# DMX_Shield_3_universe.net
KiCad netlist of a schematic drawn in EasyEDA
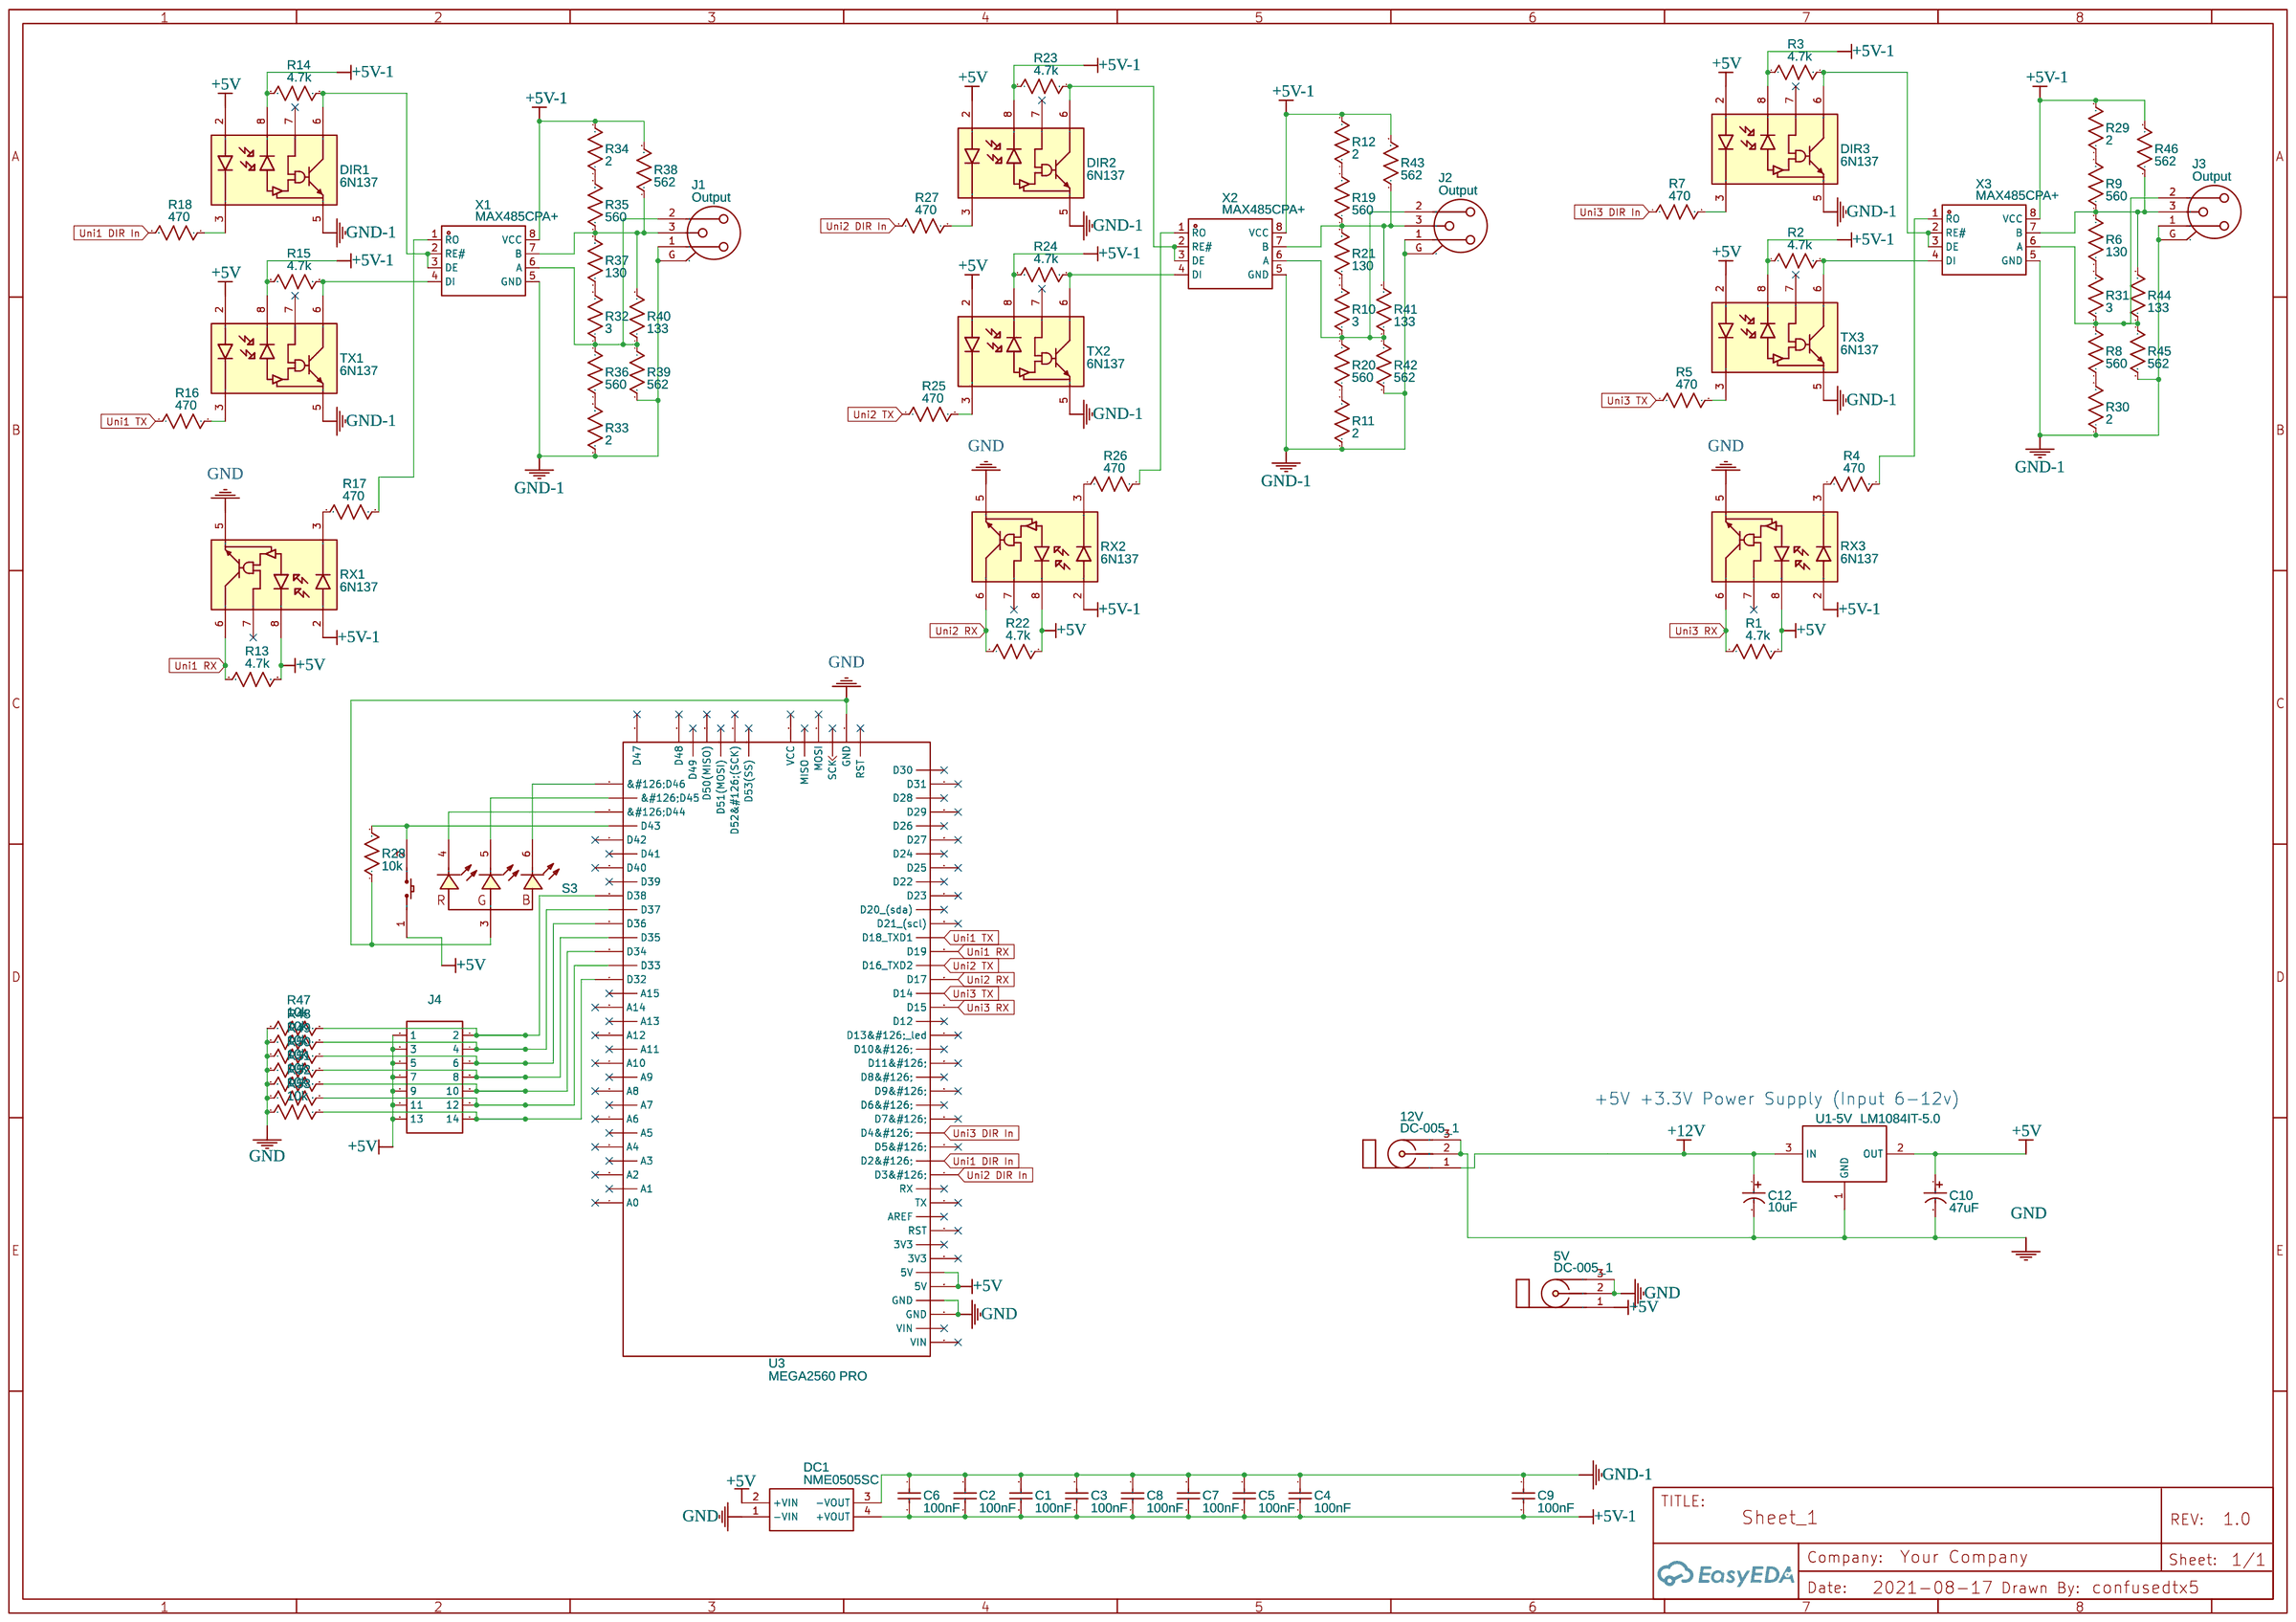
[diagram p0: schematic sheet]

(export (version "E")
  (design (tool "Eeschema 10.0.6"))
  (components
    (comp (ref "5V") (value "DC-005_1") (libsource (lib "") (part "Unknown_1125_-315")))
    (comp (ref "12V") (value "DC-005_1") (libsource (lib "") (part "Unknown_1015_-415")))
    (comp (ref "C1")
      (value "100nF")
      (fields
        (field (name "BOM_Manufacturer Part") "SR211C104KAR")
        (field (name "BOM_Supplier Part") "C444738")
      )
      (libsource (lib "") (part "SR211C104KAR"))
    )
    (comp (ref "C2")
      (value "100nF")
      (fields
        (field (name "BOM_Manufacturer Part") "SR211C104KAR")
        (field (name "BOM_Supplier Part") "C444738")
      )
      (libsource (lib "") (part "SR211C104KAR"))
    )
    (comp (ref "C3")
      (value "100nF")
      (fields
        (field (name "BOM_Manufacturer Part") "SR211C104KAR")
        (field (name "BOM_Supplier Part") "C444738")
      )
      (libsource (lib "") (part "SR211C104KAR"))
    )
    (comp (ref "C4")
      (value "100nF")
      (fields
        (field (name "BOM_Manufacturer Part") "SR211C104KAR")
        (field (name "BOM_Supplier Part") "C444738")
      )
      (libsource (lib "") (part "SR211C104KAR"))
    )
    (comp (ref "C5")
      (value "100nF")
      (fields
        (field (name "BOM_Manufacturer Part") "SR211C104KAR")
        (field (name "BOM_Supplier Part") "C444738")
      )
      (libsource (lib "") (part "SR211C104KAR"))
    )
    (comp (ref "C6")
      (value "100nF")
      (fields
        (field (name "BOM_Manufacturer Part") "SR211C104KAR")
        (field (name "BOM_Supplier Part") "C444738")
      )
      (libsource (lib "") (part "SR211C104KAR"))
    )
    (comp (ref "C7")
      (value "100nF")
      (fields
        (field (name "BOM_Manufacturer Part") "SR211C104KAR")
        (field (name "BOM_Supplier Part") "C444738")
      )
      (libsource (lib "") (part "SR211C104KAR"))
    )
    (comp (ref "C8")
      (value "100nF")
      (fields
        (field (name "BOM_Manufacturer Part") "SR211C104KAR")
        (field (name "BOM_Supplier Part") "C444738")
      )
      (libsource (lib "") (part "SR211C104KAR"))
    )
    (comp (ref "C9")
      (value "100nF")
      (fields
        (field (name "BOM_Manufacturer Part") "SR211C104KAR")
        (field (name "BOM_Supplier Part") "C444738")
      )
      (libsource (lib "") (part "SR211C104KAR"))
    )
    (comp (ref "C10")
      (value "47uF")
      (fields (field (name "BOM_Manufacturer Part") "47UF16V") (field (name "BOM_Supplier Part") "C30224"))
      (libsource (lib "") (part "47UF16V"))
    )
    (comp (ref "C12")
      (value "10uF")
      (fields
        (field (name "BOM_Manufacturer Part") "10uF 25V RHOS")
        (field (name "BOM_Supplier Part") "C19576")
      )
      (libsource (lib "") (part "Unknown_1235_-385"))
    )
    (comp (ref "DC1") (value "NME0505SC") (libsource (lib "") (part "NME0505SC")))
    (comp (ref "DIR1") (value "6N137") (libsource (lib "") (part "6N137")))
    (comp (ref "DIR2") (value "6N137") (libsource (lib "") (part "6N137")))
    (comp (ref "DIR3") (value "6N137") (libsource (lib "") (part "6N137")))
    (comp (ref "J1")
      (value "Output")
      (fields (field (name "BOM_Manufacturer Part") "XLR-328-2") (field (name "BOM_Supplier Part") "C309331"))
      (libsource (lib "") (part "XLR-328-2"))
    )
    (comp (ref "J2")
      (value "Output")
      (fields (field (name "BOM_Manufacturer Part") "XLR-328-2") (field (name "BOM_Supplier Part") "C309331"))
      (libsource (lib "") (part "XLR-328-2"))
    )
    (comp (ref "J3")
      (value "Output")
      (fields (field (name "BOM_Manufacturer Part") "XLR-328-2") (field (name "BOM_Supplier Part") "C309331"))
      (libsource (lib "") (part "XLR-328-2"))
    )
    (comp (ref "J4")
      (value "Header-Male-2.54_2x7")
      (fields
        (field (name "BOM_Manufacturer Part") "Double row of needle2X7P 2.54mm")
        (field (name "BOM_Supplier Part") "C71397")
      )
      (libsource (lib "") (part "Header-Male-2.54_2x7"))
    )
    (comp (ref "R1") (value "4.7k") (libsource (lib "") (part "R_0805_US_1")))
    (comp (ref "R2") (value "4.7k") (libsource (lib "") (part "R_0805_US_1")))
    (comp (ref "R3") (value "4.7k") (libsource (lib "") (part "R_0805_US_1")))
    (comp (ref "R4") (value "470") (libsource (lib "") (part "R_0805_US_1")))
    (comp (ref "R5") (value "470") (libsource (lib "") (part "R_0805_US_1")))
    (comp (ref "R6") (value "130") (libsource (lib "") (part "R_0805_US")))
    (comp (ref "R7") (value "470") (libsource (lib "") (part "R_0805_US_1")))
    (comp (ref "R8") (value "560") (libsource (lib "") (part "R_0805_US")))
    (comp (ref "R9") (value "560") (libsource (lib "") (part "R_0805_US")))
    (comp (ref "R10") (value "3") (libsource (lib "") (part "R_0805_US")))
    (comp (ref "R11") (value "2") (libsource (lib "") (part "R_0805_US")))
    (comp (ref "R12") (value "2") (libsource (lib "") (part "R_0805_US")))
    (comp (ref "R13") (value "4.7k") (libsource (lib "") (part "R_0805_US_1")))
    (comp (ref "R14") (value "4.7k") (libsource (lib "") (part "R_0805_US_1")))
    (comp (ref "R15") (value "4.7k") (libsource (lib "") (part "R_0805_US_1")))
    (comp (ref "R16") (value "470") (libsource (lib "") (part "R_0805_US_1")))
    (comp (ref "R17") (value "470") (libsource (lib "") (part "R_0805_US_1")))
    (comp (ref "R18") (value "470") (libsource (lib "") (part "R_0805_US_1")))
    (comp (ref "R19") (value "560") (libsource (lib "") (part "R_0805_US")))
    (comp (ref "R20") (value "560") (libsource (lib "") (part "R_0805_US")))
    (comp (ref "R21") (value "130") (libsource (lib "") (part "R_0805_US")))
    (comp (ref "R22") (value "4.7k") (libsource (lib "") (part "R_0805_US_1")))
    (comp (ref "R23") (value "4.7k") (libsource (lib "") (part "R_0805_US_1")))
    (comp (ref "R24") (value "4.7k") (libsource (lib "") (part "R_0805_US_1")))
    (comp (ref "R25") (value "470") (libsource (lib "") (part "R_0805_US_1")))
    (comp (ref "R26") (value "470") (libsource (lib "") (part "R_0805_US_1")))
    (comp (ref "R27") (value "470") (libsource (lib "") (part "R_0805_US_1")))
    (comp (ref "R28") (value "10k") (libsource (lib "") (part "R_0805_US")))
    (comp (ref "R29") (value "2") (libsource (lib "") (part "R_0805_US")))
    (comp (ref "R30") (value "2") (libsource (lib "") (part "R_0805_US")))
    (comp (ref "R31") (value "3") (libsource (lib "") (part "R_0805_US")))
    (comp (ref "R32") (value "3") (libsource (lib "") (part "R_0805_US")))
    (comp (ref "R33") (value "2") (libsource (lib "") (part "R_0805_US")))
    (comp (ref "R34") (value "2") (libsource (lib "") (part "R_0805_US")))
    (comp (ref "R35") (value "560") (libsource (lib "") (part "R_0805_US")))
    (comp (ref "R36") (value "560") (libsource (lib "") (part "R_0805_US")))
    (comp (ref "R37") (value "130") (libsource (lib "") (part "R_0805_US")))
    (comp (ref "R38") (value "562") (libsource (lib "") (part "R_0805_US")))
    (comp (ref "R39") (value "562") (libsource (lib "") (part "R_0805_US_2")))
    (comp (ref "R40") (value "133") (libsource (lib "") (part "R_0805_US")))
    (comp (ref "R41") (value "133") (libsource (lib "") (part "R_0805_US")))
    (comp (ref "R42") (value "562") (libsource (lib "") (part "R_0805_US_2")))
    (comp (ref "R43") (value "562") (libsource (lib "") (part "R_0805_US")))
    (comp (ref "R44") (value "133") (libsource (lib "") (part "R_0805_US")))
    (comp (ref "R45") (value "562") (libsource (lib "") (part "R_0805_US_2")))
    (comp (ref "R46") (value "562") (libsource (lib "") (part "R_0805_US")))
    (comp (ref "R47") (value "10k") (libsource (lib "") (part "R_0805_US_1")))
    (comp (ref "R48") (value "10k") (libsource (lib "") (part "R_0805_US_1")))
    (comp (ref "R49") (value "10k") (libsource (lib "") (part "R_0805_US_1")))
    (comp (ref "R50") (value "10k") (libsource (lib "") (part "R_0805_US_1")))
    (comp (ref "R51") (value "10k") (libsource (lib "") (part "R_0805_US_1")))
    (comp (ref "R52") (value "10k") (libsource (lib "") (part "R_0805_US_1")))
    (comp (ref "R53") (value "10k") (libsource (lib "") (part "R_0805_US_1")))
    (comp (ref "RX1") (value "6N137") (libsource (lib "") (part "6N137_1")))
    (comp (ref "RX2") (value "6N137") (libsource (lib "") (part "6N137_1")))
    (comp (ref "RX3") (value "6N137") (libsource (lib "") (part "6N137_1")))
    (comp (ref "S3") (value "RGB CA MOMENTARY BUTTON") (libsource (lib "") (part "RGB CA MOMENTARY BUTTON")))
    (comp (ref "TX1") (value "6N137") (libsource (lib "") (part "6N137_2")))
    (comp (ref "TX2") (value "6N137") (libsource (lib "") (part "6N137_2")))
    (comp (ref "TX3") (value "6N137") (libsource (lib "") (part "6N137_2")))
    (comp (ref "U1-5V")
      (value "LM1084IT-5.0")
      (fields (field (name "BOM_Supplier Part") "C9719"))
      (libsource (lib "") (part "LM1084IT-5.0"))
    )
    (comp (ref "U3")
      (value "MEGA2560 PRO")
      (fields (field (name "BOM_Manufacturer Part") "MEGA2560 PRO-ch340G"))
      (libsource (lib "") (part "MEGA2560 PRO"))
    )
    (comp (ref "X1")
      (value "MAX485CPA+")
      (fields (field (name "BOM_Supplier Part") "C77792"))
      (libsource (lib "") (part "MAX485CPA+"))
    )
    (comp (ref "X2")
      (value "MAX485CPA+")
      (fields (field (name "BOM_Supplier Part") "C77792"))
      (libsource (lib "") (part "MAX485CPA+"))
    )
    (comp (ref "X3")
      (value "MAX485CPA+")
      (fields (field (name "BOM_Supplier Part") "C77792"))
      (libsource (lib "") (part "MAX485CPA+"))
    )
  )
  (nets
    (net (code "1") (name "+5V") (class "Default")
      (node (ref "5V") (pin "1") (pinfunction "1_1") (pintype "input"))
      (node (ref "C10") (pin "1") (pinfunction "1_1") (pintype "input"))
      (node (ref "DC1") (pin "2") (pinfunction "+VIN_2") (pintype "unspecified"))
      (node (ref "DIR1") (pin "2") (pinfunction "2_2") (pintype "unspecified"))
      (node (ref "DIR2") (pin "2") (pinfunction "2_2") (pintype "unspecified"))
      (node (ref "DIR3") (pin "2") (pinfunction "2_2") (pintype "unspecified"))
      (node (ref "J4") (pin "1") (pinfunction "1_1") (pintype "input"))
      (node (ref "J4") (pin "11") (pinfunction "11_11") (pintype "input"))
      (node (ref "J4") (pin "13") (pinfunction "13_13") (pintype "input"))
      (node (ref "J4") (pin "3") (pinfunction "3_3") (pintype "input"))
      (node (ref "J4") (pin "5") (pinfunction "5_5") (pintype "input"))
      (node (ref "J4") (pin "7") (pinfunction "7_7") (pintype "input"))
      (node (ref "J4") (pin "9") (pinfunction "9_9") (pintype "input"))
      (node (ref "R1") (pin "2") (pinfunction "2_2") (pintype "unspecified"))
      (node (ref "R13") (pin "2") (pinfunction "2_2") (pintype "unspecified"))
      (node (ref "R22") (pin "2") (pinfunction "2_2") (pintype "unspecified"))
      (node (ref "RX1") (pin "8") (pinfunction "8_8") (pintype "unspecified"))
      (node (ref "RX2") (pin "8") (pinfunction "8_8") (pintype "unspecified"))
      (node (ref "RX3") (pin "8") (pinfunction "8_8") (pintype "unspecified"))
      (node (ref "S3") (pin "1") (pinfunction "NO1_1") (pintype "unspecified"))
      (node (ref "TX1") (pin "2") (pinfunction "2_2") (pintype "unspecified"))
      (node (ref "TX2") (pin "2") (pinfunction "2_2") (pintype "unspecified"))
      (node (ref "TX3") (pin "2") (pinfunction "2_2") (pintype "unspecified"))
      (node (ref "U1-5V") (pin "2") (pinfunction "OUT_2") (pintype "passive"))
      (node (ref "U3") (pin "81") (pinfunction "5V_81") (pintype "unspecified"))
      (node (ref "U3") (pin "82") (pinfunction "5V_82") (pintype "unspecified"))
    )
    (net (code "2") (name "+5V-1") (class "Default")
      (node (ref "C1") (pin "2") (pinfunction "2_2") (pintype "input"))
      (node (ref "C2") (pin "2") (pinfunction "2_2") (pintype "input"))
      (node (ref "C3") (pin "2") (pinfunction "2_2") (pintype "input"))
      (node (ref "C4") (pin "2") (pinfunction "2_2") (pintype "input"))
      (node (ref "C5") (pin "2") (pinfunction "2_2") (pintype "input"))
      (node (ref "C6") (pin "2") (pinfunction "2_2") (pintype "input"))
      (node (ref "C7") (pin "2") (pinfunction "2_2") (pintype "input"))
      (node (ref "C8") (pin "2") (pinfunction "2_2") (pintype "input"))
      (node (ref "C9") (pin "2") (pinfunction "2_2") (pintype "input"))
      (node (ref "DC1") (pin "4") (pinfunction "+VOUT_4") (pintype "unspecified"))
      (node (ref "DIR1") (pin "8") (pinfunction "8_8") (pintype "unspecified"))
      (node (ref "DIR2") (pin "8") (pinfunction "8_8") (pintype "unspecified"))
      (node (ref "DIR3") (pin "8") (pinfunction "8_8") (pintype "unspecified"))
      (node (ref "R12") (pin "2") (pinfunction "2_2") (pintype "unspecified"))
      (node (ref "R14") (pin "1") (pinfunction "1_1") (pintype "unspecified"))
      (node (ref "R15") (pin "1") (pinfunction "1_1") (pintype "unspecified"))
      (node (ref "R2") (pin "1") (pinfunction "1_1") (pintype "unspecified"))
      (node (ref "R23") (pin "1") (pinfunction "1_1") (pintype "unspecified"))
      (node (ref "R24") (pin "1") (pinfunction "1_1") (pintype "unspecified"))
      (node (ref "R29") (pin "2") (pinfunction "2_2") (pintype "unspecified"))
      (node (ref "R3") (pin "1") (pinfunction "1_1") (pintype "unspecified"))
      (node (ref "R34") (pin "2") (pinfunction "2_2") (pintype "unspecified"))
      (node (ref "R38") (pin "2") (pinfunction "2_2") (pintype "unspecified"))
      (node (ref "R43") (pin "2") (pinfunction "2_2") (pintype "unspecified"))
      (node (ref "R46") (pin "2") (pinfunction "2_2") (pintype "unspecified"))
      (node (ref "RX1") (pin "2") (pinfunction "2_2") (pintype "unspecified"))
      (node (ref "RX2") (pin "2") (pinfunction "2_2") (pintype "unspecified"))
      (node (ref "RX3") (pin "2") (pinfunction "2_2") (pintype "unspecified"))
      (node (ref "TX1") (pin "8") (pinfunction "8_8") (pintype "unspecified"))
      (node (ref "TX2") (pin "8") (pinfunction "8_8") (pintype "unspecified"))
      (node (ref "TX3") (pin "8") (pinfunction "8_8") (pintype "unspecified"))
      (node (ref "X1") (pin "8") (pinfunction "VCC_8") (pintype "unspecified"))
      (node (ref "X2") (pin "8") (pinfunction "VCC_8") (pintype "unspecified"))
      (node (ref "X3") (pin "8") (pinfunction "VCC_8") (pintype "unspecified"))
    )
    (net (code "3") (name "+12V") (class "Default")
      (node (ref "12V") (pin "1") (pinfunction "1_1") (pintype "input"))
      (node (ref "C12") (pin "1") (pinfunction "1_1") (pintype "input"))
      (node (ref "U1-5V") (pin "3") (pinfunction "IN_3") (pintype "passive"))
    )
    (net (code "4") (name "GND") (class "Default")
      (node (ref "12V") (pin "2") (pinfunction "VCC_2") (pintype "input"))
      (node (ref "12V") (pin "3") (pinfunction "3_3") (pintype "input"))
      (node (ref "5V") (pin "2") (pinfunction "VCC_2") (pintype "input"))
      (node (ref "5V") (pin "3") (pinfunction "3_3") (pintype "input"))
      (node (ref "C10") (pin "2") (pinfunction "2_2") (pintype "input"))
      (node (ref "C12") (pin "2") (pinfunction "2_2") (pintype "input"))
      (node (ref "DC1") (pin "1") (pinfunction "-VIN_1") (pintype "unspecified"))
      (node (ref "R28") (pin "1") (pinfunction "1_1") (pintype "unspecified"))
      (node (ref "R47") (pin "1") (pinfunction "1_1") (pintype "unspecified"))
      (node (ref "R48") (pin "1") (pinfunction "1_1") (pintype "unspecified"))
      (node (ref "R49") (pin "1") (pinfunction "1_1") (pintype "unspecified"))
      (node (ref "R50") (pin "1") (pinfunction "1_1") (pintype "unspecified"))
      (node (ref "R51") (pin "1") (pinfunction "1_1") (pintype "unspecified"))
      (node (ref "R52") (pin "1") (pinfunction "1_1") (pintype "unspecified"))
      (node (ref "R53") (pin "1") (pinfunction "1_1") (pintype "unspecified"))
      (node (ref "RX1") (pin "5") (pinfunction "5_5") (pintype "unspecified"))
      (node (ref "RX2") (pin "5") (pinfunction "5_5") (pintype "unspecified"))
      (node (ref "RX3") (pin "5") (pinfunction "5_5") (pintype "unspecified"))
      (node (ref "S3") (pin "3") (pinfunction "CA_3") (pintype "unspecified"))
      (node (ref "U1-5V") (pin "1") (pinfunction "GND_1") (pintype "passive"))
      (node (ref "U3") (pin "43") (pinfunction "GND_43") (pintype "unspecified"))
      (node (ref "U3") (pin "83") (pinfunction "GND_83") (pintype "unspecified"))
      (node (ref "U3") (pin "84") (pinfunction "GND_84") (pintype "unspecified"))
    )
    (net (code "5") (name "GND-1") (class "Default")
      (node (ref "C1") (pin "1") (pinfunction "1_1") (pintype "input"))
      (node (ref "C2") (pin "1") (pinfunction "1_1") (pintype "input"))
      (node (ref "C3") (pin "1") (pinfunction "1_1") (pintype "input"))
      (node (ref "C4") (pin "1") (pinfunction "1_1") (pintype "input"))
      (node (ref "C5") (pin "1") (pinfunction "1_1") (pintype "input"))
      (node (ref "C6") (pin "1") (pinfunction "1_1") (pintype "input"))
      (node (ref "C7") (pin "1") (pinfunction "1_1") (pintype "input"))
      (node (ref "C8") (pin "1") (pinfunction "1_1") (pintype "input"))
      (node (ref "C9") (pin "1") (pinfunction "1_1") (pintype "input"))
      (node (ref "DC1") (pin "3") (pinfunction "-VOUT_3") (pintype "unspecified"))
      (node (ref "DIR1") (pin "5") (pinfunction "5_5") (pintype "unspecified"))
      (node (ref "DIR2") (pin "5") (pinfunction "5_5") (pintype "unspecified"))
      (node (ref "DIR3") (pin "5") (pinfunction "5_5") (pintype "unspecified"))
      (node (ref "J1") (pin "1") (pinfunction "1_1") (pintype "unspecified"))
      (node (ref "J1") (pin "G") (pinfunction "G_G") (pintype "unspecified"))
      (node (ref "J2") (pin "1") (pinfunction "1_1") (pintype "unspecified"))
      (node (ref "J2") (pin "G") (pinfunction "G_G") (pintype "unspecified"))
      (node (ref "J3") (pin "1") (pinfunction "1_1") (pintype "unspecified"))
      (node (ref "J3") (pin "G") (pinfunction "G_G") (pintype "unspecified"))
      (node (ref "R11") (pin "1") (pinfunction "1_1") (pintype "unspecified"))
      (node (ref "R30") (pin "1") (pinfunction "1_1") (pintype "unspecified"))
      (node (ref "R33") (pin "1") (pinfunction "1_1") (pintype "unspecified"))
      (node (ref "R39") (pin "2") (pinfunction "2_2") (pintype "unspecified"))
      (node (ref "R42") (pin "2") (pinfunction "2_2") (pintype "unspecified"))
      (node (ref "R45") (pin "2") (pinfunction "2_2") (pintype "unspecified"))
      (node (ref "TX1") (pin "5") (pinfunction "5_5") (pintype "unspecified"))
      (node (ref "TX2") (pin "5") (pinfunction "5_5") (pintype "unspecified"))
      (node (ref "TX3") (pin "5") (pinfunction "5_5") (pintype "unspecified"))
      (node (ref "X1") (pin "5") (pinfunction "GND_5") (pintype "unspecified"))
      (node (ref "X2") (pin "5") (pinfunction "GND_5") (pintype "unspecified"))
      (node (ref "X3") (pin "5") (pinfunction "GND_5") (pintype "unspecified"))
    )
    (net (code "6") (name "Net-(DIR1-Pad3)") (class "Default")
      (node (ref "DIR1") (pin "3") (pinfunction "3_3") (pintype "unspecified"))
      (node (ref "R18") (pin "2") (pinfunction "2_2") (pintype "unspecified"))
    )
    (net (code "7") (name "Net-(DIR2-Pad3)") (class "Default")
      (node (ref "DIR2") (pin "3") (pinfunction "3_3") (pintype "unspecified"))
      (node (ref "R27") (pin "2") (pinfunction "2_2") (pintype "unspecified"))
    )
    (net (code "8") (name "Net-(DIR3-Pad3)") (class "Default")
      (node (ref "DIR3") (pin "3") (pinfunction "3_3") (pintype "unspecified"))
      (node (ref "R7") (pin "2") (pinfunction "2_2") (pintype "unspecified"))
    )
    (net (code "9") (name "Net-(R4-Pad1)") (class "Default")
      (node (ref "R4") (pin "1") (pinfunction "1_1") (pintype "unspecified"))
      (node (ref "RX3") (pin "3") (pinfunction "3_3") (pintype "unspecified"))
    )
    (net (code "10") (name "Net-(R5-Pad2)") (class "Default")
      (node (ref "R5") (pin "2") (pinfunction "2_2") (pintype "unspecified"))
      (node (ref "TX3") (pin "3") (pinfunction "3_3") (pintype "unspecified"))
    )
    (net (code "11") (name "Net-(R10-Pad2)") (class "Default")
      (node (ref "R10") (pin "2") (pinfunction "2_2") (pintype "unspecified"))
      (node (ref "R21") (pin "1") (pinfunction "1_1") (pintype "unspecified"))
    )
    (net (code "12") (name "Net-(R11-Pad2)") (class "Default")
      (node (ref "R11") (pin "2") (pinfunction "2_2") (pintype "unspecified"))
      (node (ref "R20") (pin "1") (pinfunction "1_1") (pintype "unspecified"))
    )
    (net (code "13") (name "Net-(R12-Pad1)") (class "Default")
      (node (ref "R12") (pin "1") (pinfunction "1_1") (pintype "unspecified"))
      (node (ref "R19") (pin "2") (pinfunction "2_2") (pintype "unspecified"))
    )
    (net (code "14") (name "Net-(R16-Pad2)") (class "Default")
      (node (ref "R16") (pin "2") (pinfunction "2_2") (pintype "unspecified"))
      (node (ref "TX1") (pin "3") (pinfunction "3_3") (pintype "unspecified"))
    )
    (net (code "15") (name "Net-(R17-Pad1)") (class "Default")
      (node (ref "R17") (pin "1") (pinfunction "1_1") (pintype "unspecified"))
      (node (ref "RX1") (pin "3") (pinfunction "3_3") (pintype "unspecified"))
    )
    (net (code "16") (name "Net-(R25-Pad2)") (class "Default")
      (node (ref "R25") (pin "2") (pinfunction "2_2") (pintype "unspecified"))
      (node (ref "TX2") (pin "3") (pinfunction "3_3") (pintype "unspecified"))
    )
    (net (code "17") (name "Net-(R26-Pad1)") (class "Default")
      (node (ref "R26") (pin "1") (pinfunction "1_1") (pintype "unspecified"))
      (node (ref "RX2") (pin "3") (pinfunction "3_3") (pintype "unspecified"))
    )
    (net (code "18") (name "Net-(R29-Pad1)") (class "Default")
      (node (ref "R29") (pin "1") (pinfunction "1_1") (pintype "unspecified"))
      (node (ref "R9") (pin "2") (pinfunction "2_2") (pintype "unspecified"))
    )
    (net (code "19") (name "Net-(R30-Pad2)") (class "Default")
      (node (ref "R30") (pin "2") (pinfunction "2_2") (pintype "unspecified"))
      (node (ref "R8") (pin "1") (pinfunction "1_1") (pintype "unspecified"))
    )
    (net (code "20") (name "Net-(R31-Pad2)") (class "Default")
      (node (ref "R31") (pin "2") (pinfunction "2_2") (pintype "unspecified"))
      (node (ref "R6") (pin "1") (pinfunction "1_1") (pintype "unspecified"))
    )
    (net (code "21") (name "Net-(R32-Pad2)") (class "Default")
      (node (ref "R32") (pin "2") (pinfunction "2_2") (pintype "unspecified"))
      (node (ref "R37") (pin "1") (pinfunction "1_1") (pintype "unspecified"))
    )
    (net (code "22") (name "Net-(R33-Pad2)") (class "Default")
      (node (ref "R33") (pin "2") (pinfunction "2_2") (pintype "unspecified"))
      (node (ref "R36") (pin "1") (pinfunction "1_1") (pintype "unspecified"))
    )
    (net (code "23") (name "Net-(R34-Pad1)") (class "Default")
      (node (ref "R34") (pin "1") (pinfunction "1_1") (pintype "unspecified"))
      (node (ref "R35") (pin "2") (pinfunction "2_2") (pintype "unspecified"))
    )
    (net (code "24") (name "Net-(S3-KB)") (class "Default")
      (node (ref "S3") (pin "6") (pinfunction "KB_6") (pintype "unspecified"))
      (node (ref "U3") (pin "31") (pinfunction "&#126;D46_31") (pintype "unspecified"))
    )
    (net (code "25") (name "Net-(S3-KG)") (class "Default")
      (node (ref "S3") (pin "5") (pinfunction "KG_5") (pintype "unspecified"))
      (node (ref "U3") (pin "30") (pinfunction "&#126;D45_30") (pintype "unspecified"))
    )
    (net (code "26") (name "Net-(S3-KR)") (class "Default")
      (node (ref "S3") (pin "4") (pinfunction "KR_4") (pintype "unspecified"))
      (node (ref "U3") (pin "29") (pinfunction "&#126;D44_29") (pintype "unspecified"))
    )
    (net (code "27") (name "Net-(S3-NO2)") (class "Default")
      (node (ref "R28") (pin "2") (pinfunction "2_2") (pintype "unspecified"))
      (node (ref "S3") (pin "2") (pinfunction "NO2_2") (pintype "unspecified"))
      (node (ref "U3") (pin "28") (pinfunction "D43_28") (pintype "unspecified"))
    )
    (net (code "28") (name "Net-(U3-D32)") (class "Default")
      (node (ref "J4") (pin "14") (pinfunction "14_14") (pintype "input"))
      (node (ref "R53") (pin "2") (pinfunction "2_2") (pintype "unspecified"))
      (node (ref "U3") (pin "17") (pinfunction "D32_17") (pintype "unspecified"))
    )
    (net (code "29") (name "Net-(U3-D33)") (class "Default")
      (node (ref "J4") (pin "12") (pinfunction "12_12") (pintype "input"))
      (node (ref "R52") (pin "2") (pinfunction "2_2") (pintype "unspecified"))
      (node (ref "U3") (pin "18") (pinfunction "D33_18") (pintype "unspecified"))
    )
    (net (code "30") (name "Net-(U3-D34)") (class "Default")
      (node (ref "J4") (pin "10") (pinfunction "10_10") (pintype "input"))
      (node (ref "R51") (pin "2") (pinfunction "2_2") (pintype "unspecified"))
      (node (ref "U3") (pin "19") (pinfunction "D34_19") (pintype "unspecified"))
    )
    (net (code "31") (name "Net-(U3-D35)") (class "Default")
      (node (ref "J4") (pin "8") (pinfunction "8_8") (pintype "input"))
      (node (ref "R50") (pin "2") (pinfunction "2_2") (pintype "unspecified"))
      (node (ref "U3") (pin "20") (pinfunction "D35_20") (pintype "unspecified"))
    )
    (net (code "32") (name "Net-(U3-D36)") (class "Default")
      (node (ref "J4") (pin "6") (pinfunction "6_6") (pintype "input"))
      (node (ref "R49") (pin "2") (pinfunction "2_2") (pintype "unspecified"))
      (node (ref "U3") (pin "21") (pinfunction "D36_21") (pintype "unspecified"))
    )
    (net (code "33") (name "Net-(U3-D37)") (class "Default")
      (node (ref "J4") (pin "4") (pinfunction "4_4") (pintype "input"))
      (node (ref "R48") (pin "2") (pinfunction "2_2") (pintype "unspecified"))
      (node (ref "U3") (pin "22") (pinfunction "D37_22") (pintype "unspecified"))
    )
    (net (code "34") (name "Net-(U3-D38)") (class "Default")
      (node (ref "J4") (pin "2") (pinfunction "2_2") (pintype "input"))
      (node (ref "R47") (pin "2") (pinfunction "2_2") (pintype "unspecified"))
      (node (ref "U3") (pin "23") (pinfunction "D38_23") (pintype "unspecified"))
    )
    (net (code "35") (name "Net-(X1-A)") (class "Default")
      (node (ref "J1") (pin "2") (pinfunction "2_2") (pintype "unspecified"))
      (node (ref "R32") (pin "1") (pinfunction "1_1") (pintype "unspecified"))
      (node (ref "R36") (pin "2") (pinfunction "2_2") (pintype "unspecified"))
      (node (ref "R39") (pin "1") (pinfunction "1_1") (pintype "unspecified"))
      (node (ref "R40") (pin "1") (pinfunction "1_1") (pintype "unspecified"))
      (node (ref "X1") (pin "6") (pinfunction "A_6") (pintype "unspecified"))
    )
    (net (code "36") (name "Net-(X1-B)") (class "Default")
      (node (ref "J1") (pin "3") (pinfunction "3_3") (pintype "unspecified"))
      (node (ref "R35") (pin "1") (pinfunction "1_1") (pintype "unspecified"))
      (node (ref "R37") (pin "2") (pinfunction "2_2") (pintype "unspecified"))
      (node (ref "R38") (pin "1") (pinfunction "1_1") (pintype "unspecified"))
      (node (ref "R40") (pin "2") (pinfunction "2_2") (pintype "unspecified"))
      (node (ref "X1") (pin "7") (pinfunction "B_7") (pintype "unspecified"))
    )
    (net (code "37") (name "Net-(X1-DE)") (class "Default")
      (node (ref "DIR1") (pin "6") (pinfunction "6_6") (pintype "output"))
      (node (ref "R14") (pin "2") (pinfunction "2_2") (pintype "unspecified"))
      (node (ref "X1") (pin "2") (pinfunction "RE#_2") (pintype "unspecified"))
      (node (ref "X1") (pin "3") (pinfunction "DE_3") (pintype "unspecified"))
    )
    (net (code "38") (name "Net-(X1-DI)") (class "Default")
      (node (ref "R15") (pin "2") (pinfunction "2_2") (pintype "unspecified"))
      (node (ref "TX1") (pin "6") (pinfunction "6_6") (pintype "output"))
      (node (ref "X1") (pin "4") (pinfunction "DI_4") (pintype "unspecified"))
    )
    (net (code "39") (name "Net-(X1-RO)") (class "Default")
      (node (ref "R17") (pin "2") (pinfunction "2_2") (pintype "unspecified"))
      (node (ref "X1") (pin "1") (pinfunction "RO_1") (pintype "unspecified"))
    )
    (net (code "40") (name "Net-(X2-A)") (class "Default")
      (node (ref "J2") (pin "2") (pinfunction "2_2") (pintype "unspecified"))
      (node (ref "R10") (pin "1") (pinfunction "1_1") (pintype "unspecified"))
      (node (ref "R20") (pin "2") (pinfunction "2_2") (pintype "unspecified"))
      (node (ref "R41") (pin "1") (pinfunction "1_1") (pintype "unspecified"))
      (node (ref "R42") (pin "1") (pinfunction "1_1") (pintype "unspecified"))
      (node (ref "X2") (pin "6") (pinfunction "A_6") (pintype "unspecified"))
    )
    (net (code "41") (name "Net-(X2-B)") (class "Default")
      (node (ref "J2") (pin "3") (pinfunction "3_3") (pintype "unspecified"))
      (node (ref "R19") (pin "1") (pinfunction "1_1") (pintype "unspecified"))
      (node (ref "R21") (pin "2") (pinfunction "2_2") (pintype "unspecified"))
      (node (ref "R41") (pin "2") (pinfunction "2_2") (pintype "unspecified"))
      (node (ref "R43") (pin "1") (pinfunction "1_1") (pintype "unspecified"))
      (node (ref "X2") (pin "7") (pinfunction "B_7") (pintype "unspecified"))
    )
    (net (code "42") (name "Net-(X2-DE)") (class "Default")
      (node (ref "DIR2") (pin "6") (pinfunction "6_6") (pintype "output"))
      (node (ref "R23") (pin "2") (pinfunction "2_2") (pintype "unspecified"))
      (node (ref "X2") (pin "2") (pinfunction "RE#_2") (pintype "unspecified"))
      (node (ref "X2") (pin "3") (pinfunction "DE_3") (pintype "unspecified"))
    )
    (net (code "43") (name "Net-(X2-DI)") (class "Default")
      (node (ref "R24") (pin "2") (pinfunction "2_2") (pintype "unspecified"))
      (node (ref "TX2") (pin "6") (pinfunction "6_6") (pintype "output"))
      (node (ref "X2") (pin "4") (pinfunction "DI_4") (pintype "unspecified"))
    )
    (net (code "44") (name "Net-(X2-RO)") (class "Default")
      (node (ref "R26") (pin "2") (pinfunction "2_2") (pintype "unspecified"))
      (node (ref "X2") (pin "1") (pinfunction "RO_1") (pintype "unspecified"))
    )
    (net (code "45") (name "Net-(X3-A)") (class "Default")
      (node (ref "J3") (pin "2") (pinfunction "2_2") (pintype "unspecified"))
      (node (ref "R31") (pin "1") (pinfunction "1_1") (pintype "unspecified"))
      (node (ref "R44") (pin "1") (pinfunction "1_1") (pintype "unspecified"))
      (node (ref "R45") (pin "1") (pinfunction "1_1") (pintype "unspecified"))
      (node (ref "R8") (pin "2") (pinfunction "2_2") (pintype "unspecified"))
      (node (ref "X3") (pin "6") (pinfunction "A_6") (pintype "unspecified"))
    )
    (net (code "46") (name "Net-(X3-B)") (class "Default")
      (node (ref "J3") (pin "3") (pinfunction "3_3") (pintype "unspecified"))
      (node (ref "R44") (pin "2") (pinfunction "2_2") (pintype "unspecified"))
      (node (ref "R46") (pin "1") (pinfunction "1_1") (pintype "unspecified"))
      (node (ref "R6") (pin "2") (pinfunction "2_2") (pintype "unspecified"))
      (node (ref "R9") (pin "1") (pinfunction "1_1") (pintype "unspecified"))
      (node (ref "X3") (pin "7") (pinfunction "B_7") (pintype "unspecified"))
    )
    (net (code "47") (name "Net-(X3-DE)") (class "Default")
      (node (ref "DIR3") (pin "6") (pinfunction "6_6") (pintype "output"))
      (node (ref "R3") (pin "2") (pinfunction "2_2") (pintype "unspecified"))
      (node (ref "X3") (pin "2") (pinfunction "RE#_2") (pintype "unspecified"))
      (node (ref "X3") (pin "3") (pinfunction "DE_3") (pintype "unspecified"))
    )
    (net (code "48") (name "Net-(X3-DI)") (class "Default")
      (node (ref "R2") (pin "2") (pinfunction "2_2") (pintype "unspecified"))
      (node (ref "TX3") (pin "6") (pinfunction "6_6") (pintype "output"))
      (node (ref "X3") (pin "4") (pinfunction "DI_4") (pintype "unspecified"))
    )
    (net (code "49") (name "Net-(X3-RO)") (class "Default")
      (node (ref "R4") (pin "2") (pinfunction "2_2") (pintype "unspecified"))
      (node (ref "X3") (pin "1") (pinfunction "RO_1") (pintype "unspecified"))
    )
    (net (code "50") (name "Uni1 DIR In") (class "Default")
      (node (ref "R18") (pin "1") (pinfunction "1_1") (pintype "unspecified"))
      (node (ref "U3") (pin "73") (pinfunction "D2&#126;_73") (pintype "unspecified"))
    )
    (net (code "51") (name "Uni1 RX") (class "Default")
      (node (ref "R13") (pin "1") (pinfunction "1_1") (pintype "unspecified"))
      (node (ref "RX1") (pin "6") (pinfunction "6_6") (pintype "output"))
      (node (ref "U3") (pin "58") (pinfunction "D19_58") (pintype "unspecified"))
    )
    (net (code "52") (name "Uni1 TX") (class "Default")
      (node (ref "R16") (pin "1") (pinfunction "1_1") (pintype "unspecified"))
      (node (ref "U3") (pin "57") (pinfunction "D18_TXD1_57") (pintype "unspecified"))
    )
    (net (code "53") (name "Uni2 DIR In") (class "Default")
      (node (ref "R27") (pin "1") (pinfunction "1_1") (pintype "unspecified"))
      (node (ref "U3") (pin "74") (pinfunction "D3&#126;_74") (pintype "unspecified"))
    )
    (net (code "54") (name "Uni2 RX") (class "Default")
      (node (ref "R22") (pin "1") (pinfunction "1_1") (pintype "unspecified"))
      (node (ref "RX2") (pin "6") (pinfunction "6_6") (pintype "output"))
      (node (ref "U3") (pin "60") (pinfunction "D17_60") (pintype "unspecified"))
    )
    (net (code "55") (name "Uni2 TX") (class "Default")
      (node (ref "R25") (pin "1") (pinfunction "1_1") (pintype "unspecified"))
      (node (ref "U3") (pin "59") (pinfunction "D16_TXD2_59") (pintype "unspecified"))
    )
    (net (code "56") (name "Uni3 DIR In") (class "Default")
      (node (ref "R7") (pin "1") (pinfunction "1_1") (pintype "unspecified"))
      (node (ref "U3") (pin "71") (pinfunction "D4&#126;_71") (pintype "unspecified"))
    )
    (net (code "57") (name "Uni3 RX") (class "Default")
      (node (ref "R1") (pin "1") (pinfunction "1_1") (pintype "unspecified"))
      (node (ref "RX3") (pin "6") (pinfunction "6_6") (pintype "output"))
      (node (ref "U3") (pin "62") (pinfunction "D15_62") (pintype "unspecified"))
    )
    (net (code "58") (name "Uni3 TX") (class "Default")
      (node (ref "R5") (pin "1") (pinfunction "1_1") (pintype "unspecified"))
      (node (ref "U3") (pin "61") (pinfunction "D14_61") (pintype "unspecified"))
    )
    (net (code "59") (name "unconnected-(DIR1-Pad7)") (class "Default")
      (node (ref "DIR1") (pin "7") (pinfunction "7_7") (pintype "unspecified+no_connect"))
    )
    (net (code "60") (name "unconnected-(DIR2-Pad7)") (class "Default")
      (node (ref "DIR2") (pin "7") (pinfunction "7_7") (pintype "unspecified+no_connect"))
    )
    (net (code "61") (name "unconnected-(DIR3-Pad7)") (class "Default")
      (node (ref "DIR3") (pin "7") (pinfunction "7_7") (pintype "unspecified+no_connect"))
    )
    (net (code "62") (name "unconnected-(RX1-Pad7)") (class "Default")
      (node (ref "RX1") (pin "7") (pinfunction "7_7") (pintype "unspecified+no_connect"))
    )
    (net (code "63") (name "unconnected-(RX2-Pad7)") (class "Default")
      (node (ref "RX2") (pin "7") (pinfunction "7_7") (pintype "unspecified+no_connect"))
    )
    (net (code "64") (name "unconnected-(RX3-Pad7)") (class "Default")
      (node (ref "RX3") (pin "7") (pinfunction "7_7") (pintype "unspecified+no_connect"))
    )
    (net (code "65") (name "unconnected-(TX1-Pad7)") (class "Default")
      (node (ref "TX1") (pin "7") (pinfunction "7_7") (pintype "unspecified+no_connect"))
    )
    (net (code "66") (name "unconnected-(TX2-Pad7)") (class "Default")
      (node (ref "TX2") (pin "7") (pinfunction "7_7") (pintype "unspecified+no_connect"))
    )
    (net (code "67") (name "unconnected-(TX3-Pad7)") (class "Default")
      (node (ref "TX3") (pin "7") (pinfunction "7_7") (pintype "unspecified+no_connect"))
    )
    (net (code "68") (name "unconnected-(U3-3V3-Pad79)") (class "Default")
      (node (ref "U3") (pin "79") (pinfunction "3V3_79") (pintype "unspecified+no_connect"))
    )
    (net (code "69") (name "unconnected-(U3-3V3-Pad80)") (class "Default")
      (node (ref "U3") (pin "80") (pinfunction "3V3_80") (pintype "unspecified+no_connect"))
    )
    (net (code "70") (name "unconnected-(U3-A0-Pad1)") (class "Default")
      (node (ref "U3") (pin "1") (pinfunction "A0_1") (pintype "unspecified+no_connect"))
    )
    (net (code "71") (name "unconnected-(U3-A1-Pad2)") (class "Default")
      (node (ref "U3") (pin "2") (pinfunction "A1_2") (pintype "unspecified+no_connect"))
    )
    (net (code "72") (name "unconnected-(U3-A2-Pad3)") (class "Default")
      (node (ref "U3") (pin "3") (pinfunction "A2_3") (pintype "unspecified+no_connect"))
    )
    (net (code "73") (name "unconnected-(U3-A3-Pad4)") (class "Default")
      (node (ref "U3") (pin "4") (pinfunction "A3_4") (pintype "unspecified+no_connect"))
    )
    (net (code "74") (name "unconnected-(U3-A4-Pad5)") (class "Default")
      (node (ref "U3") (pin "5") (pinfunction "A4_5") (pintype "unspecified+no_connect"))
    )
    (net (code "75") (name "unconnected-(U3-A5-Pad6)") (class "Default")
      (node (ref "U3") (pin "6") (pinfunction "A5_6") (pintype "unspecified+no_connect"))
    )
    (net (code "76") (name "unconnected-(U3-A6-Pad7)") (class "Default")
      (node (ref "U3") (pin "7") (pinfunction "A6_7") (pintype "unspecified+no_connect"))
    )
    (net (code "77") (name "unconnected-(U3-A7-Pad8)") (class "Default")
      (node (ref "U3") (pin "8") (pinfunction "A7_8") (pintype "unspecified+no_connect"))
    )
    (net (code "78") (name "unconnected-(U3-A8-Pad9)") (class "Default")
      (node (ref "U3") (pin "9") (pinfunction "A8_9") (pintype "unspecified+no_connect"))
    )
    (net (code "79") (name "unconnected-(U3-A9-Pad10)") (class "Default")
      (node (ref "U3") (pin "10") (pinfunction "A9_10") (pintype "unspecified+no_connect"))
    )
    (net (code "80") (name "unconnected-(U3-A10-Pad11)") (class "Default")
      (node (ref "U3") (pin "11") (pinfunction "A10_11") (pintype "unspecified+no_connect"))
    )
    (net (code "81") (name "unconnected-(U3-A11-Pad12)") (class "Default")
      (node (ref "U3") (pin "12") (pinfunction "A11_12") (pintype "unspecified+no_connect"))
    )
    (net (code "82") (name "unconnected-(U3-A12-Pad13)") (class "Default")
      (node (ref "U3") (pin "13") (pinfunction "A12_13") (pintype "unspecified+no_connect"))
    )
    (net (code "83") (name "unconnected-(U3-A13-Pad14)") (class "Default")
      (node (ref "U3") (pin "14") (pinfunction "A13_14") (pintype "unspecified+no_connect"))
    )
    (net (code "84") (name "unconnected-(U3-A14-Pad15)") (class "Default")
      (node (ref "U3") (pin "15") (pinfunction "A14_15") (pintype "unspecified+no_connect"))
    )
    (net (code "85") (name "unconnected-(U3-A15-Pad16)") (class "Default")
      (node (ref "U3") (pin "16") (pinfunction "A15_16") (pintype "unspecified+no_connect"))
    )
    (net (code "86") (name "unconnected-(U3-AREF-Pad77)") (class "Default")
      (node (ref "U3") (pin "77") (pinfunction "AREF_77") (pintype "unspecified+no_connect"))
    )
    (net (code "87") (name "unconnected-(U3-D5&#126;-Pad72)") (class "Default")
      (node (ref "U3") (pin "72") (pinfunction "D5&#126;_72") (pintype "unspecified+no_connect"))
    )
    (net (code "88") (name "unconnected-(U3-D6&#126;-Pad69)") (class "Default")
      (node (ref "U3") (pin "69") (pinfunction "D6&#126;_69") (pintype "unspecified+no_connect"))
    )
    (net (code "89") (name "unconnected-(U3-D7&#126;-Pad70)") (class "Default")
      (node (ref "U3") (pin "70") (pinfunction "D7&#126;_70") (pintype "unspecified+no_connect"))
    )
    (net (code "90") (name "unconnected-(U3-D8&#126;-Pad67)") (class "Default")
      (node (ref "U3") (pin "67") (pinfunction "D8&#126;_67") (pintype "unspecified+no_connect"))
    )
    (net (code "91") (name "unconnected-(U3-D9&#126;-Pad68)") (class "Default")
      (node (ref "U3") (pin "68") (pinfunction "D9&#126;_68") (pintype "unspecified+no_connect"))
    )
    (net (code "92") (name "unconnected-(U3-D10&#126;-Pad65)") (class "Default")
      (node (ref "U3") (pin "65") (pinfunction "D10&#126;_65") (pintype "unspecified+no_connect"))
    )
    (net (code "93") (name "unconnected-(U3-D11&#126;-Pad66)") (class "Default")
      (node (ref "U3") (pin "66") (pinfunction "D11&#126;_66") (pintype "bidirectional+no_connect"))
    )
    (net (code "94") (name "unconnected-(U3-D12-Pad63)") (class "Default")
      (node (ref "U3") (pin "63") (pinfunction "D12_63") (pintype "unspecified+no_connect"))
    )
    (net (code "95") (name "unconnected-(U3-D13&#126;_led-Pad64)") (class "Default")
      (node (ref "U3") (pin "64") (pinfunction "D13&#126;_led_64") (pintype "unspecified+no_connect"))
    )
    (net (code "96") (name "unconnected-(U3-D20_(sda)-Pad55)") (class "Default")
      (node (ref "U3") (pin "55") (pinfunction "D20_(sda)_55") (pintype "unspecified+no_connect"))
    )
    (net (code "97") (name "unconnected-(U3-D21_(scl)-Pad56)") (class "Default")
      (node (ref "U3") (pin "56") (pinfunction "D21_(scl)_56") (pintype "unspecified+no_connect"))
    )
    (net (code "98") (name "unconnected-(U3-D22-Pad53)") (class "Default")
      (node (ref "U3") (pin "53") (pinfunction "D22_53") (pintype "unspecified+no_connect"))
    )
    (net (code "99") (name "unconnected-(U3-D23-Pad54)") (class "Default")
      (node (ref "U3") (pin "54") (pinfunction "D23_54") (pintype "unspecified+no_connect"))
    )
    (net (code "100") (name "unconnected-(U3-D24-Pad51)") (class "Default")
      (node (ref "U3") (pin "51") (pinfunction "D24_51") (pintype "unspecified+no_connect"))
    )
    (net (code "101") (name "unconnected-(U3-D25-Pad52)") (class "Default")
      (node (ref "U3") (pin "52") (pinfunction "D25_52") (pintype "unspecified+no_connect"))
    )
    (net (code "102") (name "unconnected-(U3-D26-Pad49)") (class "Default")
      (node (ref "U3") (pin "49") (pinfunction "D26_49") (pintype "unspecified+no_connect"))
    )
    (net (code "103") (name "unconnected-(U3-D27-Pad50)") (class "Default")
      (node (ref "U3") (pin "50") (pinfunction "D27_50") (pintype "unspecified+no_connect"))
    )
    (net (code "104") (name "unconnected-(U3-D28-Pad47)") (class "Default")
      (node (ref "U3") (pin "47") (pinfunction "D28_47") (pintype "unspecified+no_connect"))
    )
    (net (code "105") (name "unconnected-(U3-D29-Pad48)") (class "Default")
      (node (ref "U3") (pin "48") (pinfunction "D29_48") (pintype "unspecified+no_connect"))
    )
    (net (code "106") (name "unconnected-(U3-D30-Pad45)") (class "Default")
      (node (ref "U3") (pin "45") (pinfunction "D30_45") (pintype "unspecified+no_connect"))
    )
    (net (code "107") (name "unconnected-(U3-D31-Pad46)") (class "Default")
      (node (ref "U3") (pin "46") (pinfunction "D31_46") (pintype "unspecified+no_connect"))
    )
    (net (code "108") (name "unconnected-(U3-D39-Pad24)") (class "Default")
      (node (ref "U3") (pin "24") (pinfunction "D39_24") (pintype "unspecified+no_connect"))
    )
    (net (code "109") (name "unconnected-(U3-D40-Pad25)") (class "Default")
      (node (ref "U3") (pin "25") (pinfunction "D40_25") (pintype "unspecified+no_connect"))
    )
    (net (code "110") (name "unconnected-(U3-D41-Pad26)") (class "Default")
      (node (ref "U3") (pin "26") (pinfunction "D41_26") (pintype "unspecified+no_connect"))
    )
    (net (code "111") (name "unconnected-(U3-D42-Pad27)") (class "Default")
      (node (ref "U3") (pin "27") (pinfunction "D42_27") (pintype "unspecified+no_connect"))
    )
    (net (code "112") (name "unconnected-(U3-D47-Pad32)") (class "Default")
      (node (ref "U3") (pin "32") (pinfunction "D47_32") (pintype "unspecified+no_connect"))
    )
    (net (code "113") (name "unconnected-(U3-D48-Pad33)") (class "Default")
      (node (ref "U3") (pin "33") (pinfunction "D48_33") (pintype "unspecified+no_connect"))
    )
    (net (code "114") (name "unconnected-(U3-D49-Pad34)") (class "Default")
      (node (ref "U3") (pin "34") (pinfunction "D49_34") (pintype "unspecified+no_connect"))
    )
    (net (code "115") (name "unconnected-(U3-D50(MISO)-Pad35)") (class "Default")
      (node (ref "U3") (pin "35") (pinfunction "D50(MISO)_35") (pintype "unspecified+no_connect"))
    )
    (net (code "116") (name "unconnected-(U3-D51(MOSI)-Pad36)") (class "Default")
      (node (ref "U3") (pin "36") (pinfunction "D51(MOSI)_36") (pintype "unspecified+no_connect"))
    )
    (net (code "117") (name "unconnected-(U3-D52&#126;(SCK)-Pad37)") (class "Default")
      (node (ref "U3") (pin "37") (pinfunction "D52&#126;(SCK)_37") (pintype "unspecified+no_connect"))
    )
    (net (code "118") (name "unconnected-(U3-D53(SS)-Pad38)") (class "Default")
      (node (ref "U3") (pin "38") (pinfunction "D53(SS)_38") (pintype "unspecified+no_connect"))
    )
    (net (code "119") (name "unconnected-(U3-MISO-Pad40)") (class "Default")
      (node (ref "U3") (pin "40") (pinfunction "MISO_40") (pintype "unspecified+no_connect"))
    )
    (net (code "120") (name "unconnected-(U3-MOSI-Pad41)") (class "Default")
      (node (ref "U3") (pin "41") (pinfunction "MOSI_41") (pintype "unspecified+no_connect"))
    )
    (net (code "121") (name "unconnected-(U3-RST-Pad44)") (class "Default")
      (node (ref "U3") (pin "44") (pinfunction "RST_44") (pintype "unspecified+no_connect"))
    )
    (net (code "122") (name "unconnected-(U3-RST-Pad78)") (class "Default")
      (node (ref "U3") (pin "78") (pinfunction "RST_78") (pintype "unspecified+no_connect"))
    )
    (net (code "123") (name "unconnected-(U3-RX-Pad75)") (class "Default")
      (node (ref "U3") (pin "75") (pinfunction "RX_75") (pintype "unspecified+no_connect"))
    )
    (net (code "124") (name "unconnected-(U3-SCK-Pad42)") (class "Default")
      (node (ref "U3") (pin "42") (pinfunction "SCK_42") (pintype "unspecified+no_connect"))
    )
    (net (code "125") (name "unconnected-(U3-TX-Pad76)") (class "Default")
      (node (ref "U3") (pin "76") (pinfunction "TX_76") (pintype "unspecified+no_connect"))
    )
    (net (code "126") (name "unconnected-(U3-VCC-Pad39)") (class "Default")
      (node (ref "U3") (pin "39") (pinfunction "VCC_39") (pintype "unspecified+no_connect"))
    )
    (net (code "127") (name "unconnected-(U3-VIN-Pad85)") (class "Default")
      (node (ref "U3") (pin "85") (pinfunction "VIN_85") (pintype "unspecified+no_connect"))
    )
    (net (code "128") (name "unconnected-(U3-VIN-Pad86)") (class "Default")
      (node (ref "U3") (pin "86") (pinfunction "VIN_86") (pintype "unspecified+no_connect"))
    )
  )
)
